# PostMUX_Filter.net
KiCad netlist of a schematic drawn in Altium Designer
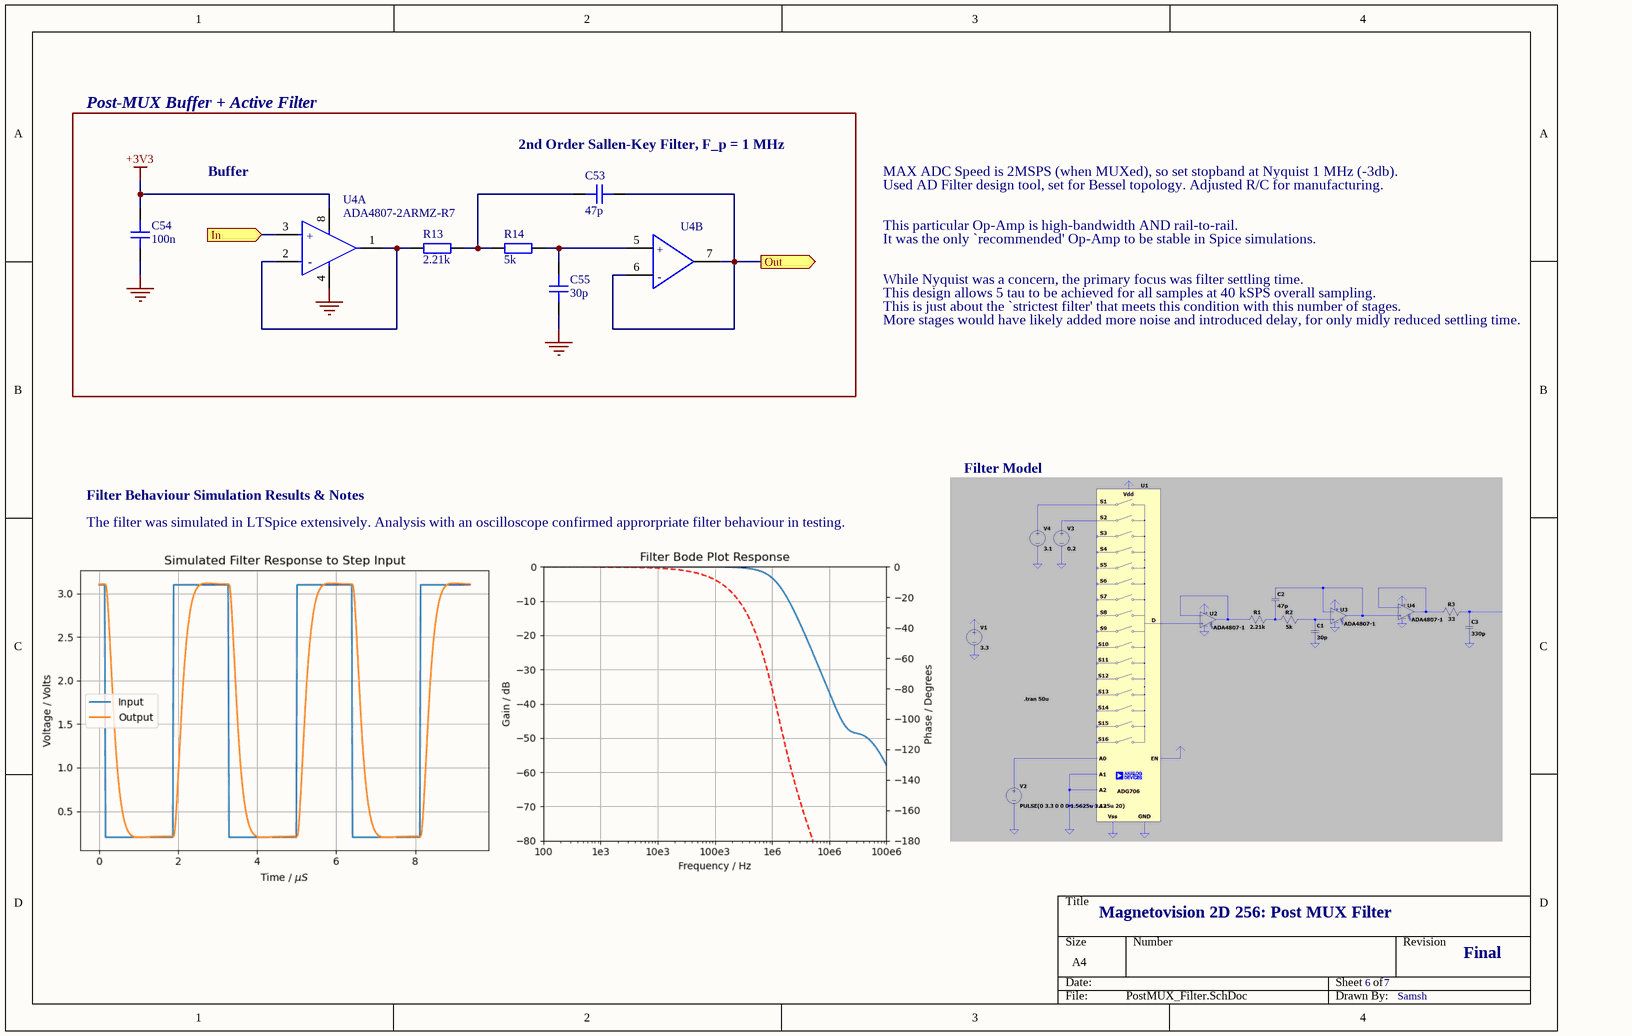
[diagram p0: PostMUX_Filter.SchDoc]

(export (version "E")
  (design (tool "Eeschema 10.0.6"))
  (components
    (comp (ref "C53")
      (value "47p")
      (footprint "CAP_0603")
      (description "Capacitor SMD 0603")
      (fields (field (name "SOURCE") "Schematic-Lib-PhilsLab.SchLib"))
      (libsource (lib "Samsh Nanoelectronics") (part "CAP_EL_NP_5MM"))
    )
    (comp (ref "C54")
      (value "100n")
      (footprint "CAP_0603")
      (description "Capacitor SMD 0603")
      (fields (field (name "SOURCE") "Schematic-Lib-PhilsLab.SchLib"))
      (libsource (lib "Samsh Nanoelectronics") (part "CAP_EL_NP_5MM"))
    )
    (comp (ref "C55")
      (value "30p")
      (footprint "CAP_0603")
      (description "Capacitor SMD 0603")
      (fields (field (name "SOURCE") "Schematic-Lib-PhilsLab.SchLib"))
      (libsource (lib "Samsh Nanoelectronics") (part "CAP_EL_NP_5MM"))
    )
    (comp (ref "R13")
      (value "2.21k")
      (footprint "RES_0603")
      (description "Resistor SMD 0603")
      (fields (field (name "SOURCE") "Schematic-Lib-PhilsLab.SchLib"))
      (libsource (lib "Samsh Nanoelectronics") (part "RES_5931"))
    )
    (comp (ref "R14")
      (value "5k")
      (footprint "RES_0603")
      (description "Resistor SMD 0603")
      (fields (field (name "SOURCE") "Schematic-Lib-PhilsLab.SchLib"))
      (libsource (lib "Samsh Nanoelectronics") (part "RES_5931"))
    )
    (comp (ref "U4")
      (value "ADA4807-2ARMZ-R7")
      (footprint "FP-RM-8-IPC_A")
      (description "IC OPAMP VFB 2 CIRCUIT 8MSOP")
      (libsource (lib "Altium Content Vault") (part "164c3b58bae7926e98bb6d8ef363a34"))
    )
  )
  (nets
    (net (code "1") (name "+3V3") (class "Default")
      (node (ref "C54") (pin "2") (pinfunction "2_2") (pintype "passive"))
      (node (ref "U4") (pin "8") (pinfunction "+VS_8") (pintype "power_in"))
    )
    (net (code "2") (name "/In") (class "Default")
      (node (ref "U4") (pin "3") (pinfunction "+IN1_3") (pintype "tri_state"))
    )
    (net (code "3") (name "/Out") (class "Default")
      (node (ref "C53") (pin "2") (pinfunction "2_2") (pintype "passive"))
      (node (ref "U4") (pin "6") (pinfunction "-IN2_6") (pintype "tri_state"))
      (node (ref "U4") (pin "7") (pinfunction "VOUT2_7") (pintype "power_in"))
    )
    (net (code "4") (name "GND") (class "Default")
      (node (ref "C54") (pin "1") (pinfunction "1_1") (pintype "passive"))
      (node (ref "C55") (pin "1") (pinfunction "1_1") (pintype "passive"))
      (node (ref "U4") (pin "4") (pinfunction "-VS_4") (pintype "power_in"))
    )
    (net (code "5") (name "Net-(C53-Pad1)") (class "Default")
      (node (ref "C53") (pin "1") (pinfunction "1_1") (pintype "passive"))
      (node (ref "R13") (pin "1") (pinfunction "1_1") (pintype "passive"))
      (node (ref "R14") (pin "2") (pinfunction "2_2") (pintype "passive"))
    )
    (net (code "6") (name "Net-(U4A--IN1)") (class "Default")
      (node (ref "R13") (pin "2") (pinfunction "2_2") (pintype "passive"))
      (node (ref "U4") (pin "1") (pinfunction "VOUT1_1") (pintype "power_in"))
      (node (ref "U4") (pin "2") (pinfunction "-IN1_2") (pintype "tri_state"))
    )
    (net (code "7") (name "Net-(U4B-+IN2)") (class "Default")
      (node (ref "C55") (pin "2") (pinfunction "2_2") (pintype "passive"))
      (node (ref "R14") (pin "1") (pinfunction "1_1") (pintype "passive"))
      (node (ref "U4") (pin "5") (pinfunction "+IN2_5") (pintype "tri_state"))
    )
  )
)
